# Analog.net
KiCad netlist of a schematic drawn in Altium Designer
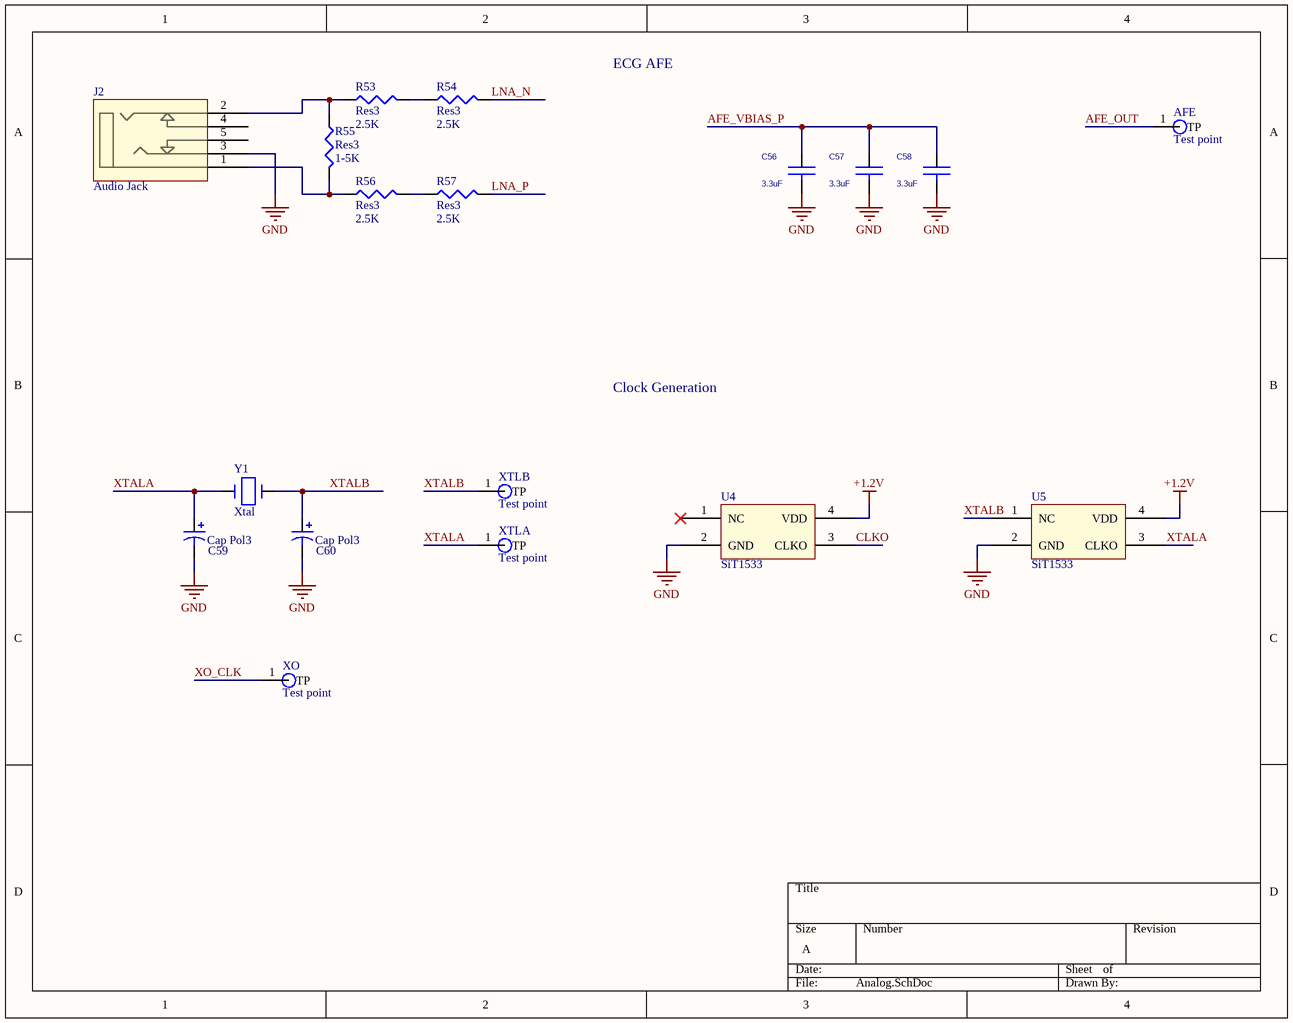
[diagram p0: Analog.SchDoc]

(export (version "E")
  (design (tool "Eeschema 10.0.6"))
  (components
    (comp (ref "AFE") (value "Test point") (footprint "TP") (libsource (lib "INERTIA") (part "Test point")))
    (comp (ref "C56") (value "3.3uF") (footprint "0402") (libsource (lib "*") (part "C")))
    (comp (ref "C57") (value "3.3uF") (footprint "0402") (libsource (lib "*") (part "C")))
    (comp (ref "C58") (value "3.3uF") (footprint "0402") (libsource (lib "*") (part "C")))
    (comp (ref "C59")
      (value "Cap Pol3")
      (footprint "0402")
      (description "Polarized Capacitor (Surface Mount)")
      (fields (field (name "PUBLISHER") "Altium Limited"))
      (libsource (lib "Miscellaneous Devices") (part "Cap Pol3"))
    )
    (comp (ref "C60")
      (value "Cap Pol3")
      (footprint "0402")
      (description "Polarized Capacitor (Surface Mount)")
      (fields (field (name "PUBLISHER") "Altium Limited"))
      (libsource (lib "Miscellaneous Devices") (part "Cap Pol3"))
    )
    (comp (ref "J2")
      (value "Audio Jack")
      (footprint "Audio Jack")
      (libsource (lib "INERTIA") (part "Audio Jack"))
    )
    (comp (ref "R53")
      (value "Res3")
      (footprint "0402")
      (description "Resistor")
      (fields (field (name "ALTIUM_VALUE") "2.5K") (field (name "PUBLISHER") "Altium Limited"))
      (libsource (lib "Miscellaneous Devices") (part "Res3"))
    )
    (comp (ref "R54")
      (value "Res3")
      (footprint "0402")
      (description "Resistor")
      (fields (field (name "ALTIUM_VALUE") "2.5K") (field (name "PUBLISHER") "Altium Limited"))
      (libsource (lib "Miscellaneous Devices") (part "Res3"))
    )
    (comp (ref "R55")
      (value "Res3")
      (footprint "0402")
      (description "Resistor")
      (fields (field (name "ALTIUM_VALUE") "1-5K") (field (name "PUBLISHER") "Altium Limited"))
      (libsource (lib "Miscellaneous Devices") (part "Res3"))
    )
    (comp (ref "R56")
      (value "Res3")
      (footprint "0402")
      (description "Resistor")
      (fields (field (name "ALTIUM_VALUE") "2.5K") (field (name "PUBLISHER") "Altium Limited"))
      (libsource (lib "Miscellaneous Devices") (part "Res3"))
    )
    (comp (ref "R57")
      (value "Res3")
      (footprint "0402")
      (description "Resistor")
      (fields (field (name "ALTIUM_VALUE") "2.5K") (field (name "PUBLISHER") "Altium Limited"))
      (libsource (lib "Miscellaneous Devices") (part "Res3"))
    )
    (comp (ref "U4")
      (value "SiT1533")
      (footprint "SiT1533")
      (description "Ultra-low Power 32KHz Oscillator")
      (libsource (lib "INERTIA") (part "SiT1533"))
    )
    (comp (ref "U5")
      (value "SiT1533")
      (footprint "SiT1533")
      (description "Ultra-low Power 32KHz Oscillator")
      (libsource (lib "INERTIA") (part "SiT1533"))
    )
    (comp (ref "XO") (value "Test point") (footprint "TP") (libsource (lib "INERTIA") (part "Test point")))
    (comp (ref "XTLA") (value "Test point") (footprint "TP") (libsource (lib "INERTIA") (part "Test point")))
    (comp (ref "XTLB") (value "Test point") (footprint "TP") (libsource (lib "INERTIA") (part "Test point")))
    (comp (ref "Y1") (value "Xtal") (footprint "Xtal_C2") (libsource (lib "INERTIA") (part "Xtal")))
  )
  (nets
    (net (code "1") (name "+1.2V") (class "Default")
      (node (ref "U4") (pin "4") (pinfunction "VDD_4") (pintype "passive"))
      (node (ref "U5") (pin "4") (pinfunction "VDD_4") (pintype "passive"))
    )
    (net (code "2") (name "/AFE_OUT") (class "Default")
      (node (ref "AFE") (pin "1") (pinfunction "TP_1") (pintype "passive"))
    )
    (net (code "3") (name "/AFE_VBIAS_P") (class "Default")
      (node (ref "C56") (pin "1") (pinfunction "1_1") (pintype "passive"))
      (node (ref "C57") (pin "1") (pinfunction "1_1") (pintype "passive"))
      (node (ref "C58") (pin "1") (pinfunction "1_1") (pintype "passive"))
    )
    (net (code "4") (name "/CLKO") (class "Default")
      (node (ref "U4") (pin "3") (pinfunction "CLKO_3") (pintype "passive"))
    )
    (net (code "5") (name "/LNA_N") (class "Default")
      (node (ref "R54") (pin "2") (pinfunction "2_2") (pintype "passive"))
    )
    (net (code "6") (name "/LNA_P") (class "Default")
      (node (ref "R57") (pin "2") (pinfunction "2_2") (pintype "passive"))
    )
    (net (code "7") (name "/XO_CLK") (class "Default")
      (node (ref "XO") (pin "1") (pinfunction "TP_1") (pintype "passive"))
    )
    (net (code "8") (name "/XTALA") (class "Default")
      (node (ref "C59") (pin "1") (pinfunction "1_1") (pintype "passive"))
      (node (ref "U5") (pin "3") (pinfunction "CLKO_3") (pintype "passive"))
      (node (ref "XTLA") (pin "1") (pinfunction "TP_1") (pintype "passive"))
      (node (ref "Y1") (pin "1") (pinfunction "1_1") (pintype "passive"))
    )
    (net (code "9") (name "/XTALB") (class "Default")
      (node (ref "C60") (pin "1") (pinfunction "1_1") (pintype "passive"))
      (node (ref "U5") (pin "1") (pinfunction "NC_1") (pintype "passive"))
      (node (ref "XTLB") (pin "1") (pinfunction "TP_1") (pintype "passive"))
      (node (ref "Y1") (pin "2") (pinfunction "2_2") (pintype "passive"))
    )
    (net (code "10") (name "GND") (class "Default")
      (node (ref "C56") (pin "2") (pinfunction "2_2") (pintype "passive"))
      (node (ref "C57") (pin "2") (pinfunction "2_2") (pintype "passive"))
      (node (ref "C58") (pin "2") (pinfunction "2_2") (pintype "passive"))
      (node (ref "C59") (pin "2") (pinfunction "2_2") (pintype "passive"))
      (node (ref "C60") (pin "2") (pinfunction "2_2") (pintype "passive"))
      (node (ref "J2") (pin "3") (pinfunction "3_3") (pintype "passive"))
      (node (ref "U4") (pin "2") (pinfunction "GND_2") (pintype "passive"))
      (node (ref "U5") (pin "2") (pinfunction "GND_2") (pintype "passive"))
    )
    (net (code "11") (name "Net-(J2-Pad1)") (class "Default")
      (node (ref "J2") (pin "1") (pinfunction "1_1") (pintype "passive"))
      (node (ref "R55") (pin "2") (pinfunction "2_2") (pintype "passive"))
      (node (ref "R56") (pin "1") (pinfunction "1_1") (pintype "passive"))
    )
    (net (code "12") (name "Net-(J2-Pad2)") (class "Default")
      (node (ref "J2") (pin "2") (pinfunction "2_2") (pintype "passive"))
      (node (ref "R53") (pin "1") (pinfunction "1_1") (pintype "passive"))
      (node (ref "R55") (pin "1") (pinfunction "1_1") (pintype "passive"))
    )
    (net (code "13") (name "Net-(R53-Pad2)") (class "Default")
      (node (ref "R53") (pin "2") (pinfunction "2_2") (pintype "passive"))
      (node (ref "R54") (pin "1") (pinfunction "1_1") (pintype "passive"))
    )
    (net (code "14") (name "Net-(R56-Pad2)") (class "Default")
      (node (ref "R56") (pin "2") (pinfunction "2_2") (pintype "passive"))
      (node (ref "R57") (pin "1") (pinfunction "1_1") (pintype "passive"))
    )
    (net (code "15") (name "unconnected-(J2-Pad4)") (class "Default")
      (node (ref "J2") (pin "4") (pinfunction "4_4") (pintype "passive"))
    )
    (net (code "16") (name "unconnected-(J2-Pad5)") (class "Default")
      (node (ref "J2") (pin "5") (pinfunction "5_5") (pintype "passive"))
    )
    (net (code "17") (name "unconnected-(U4-NC-Pad1)") (class "Default")
      (node (ref "U4") (pin "1") (pinfunction "NC_1") (pintype "passive+no_connect"))
    )
  )
)
